# ADD_1_1.net
KiCad netlist of a schematic drawn in EAGLE
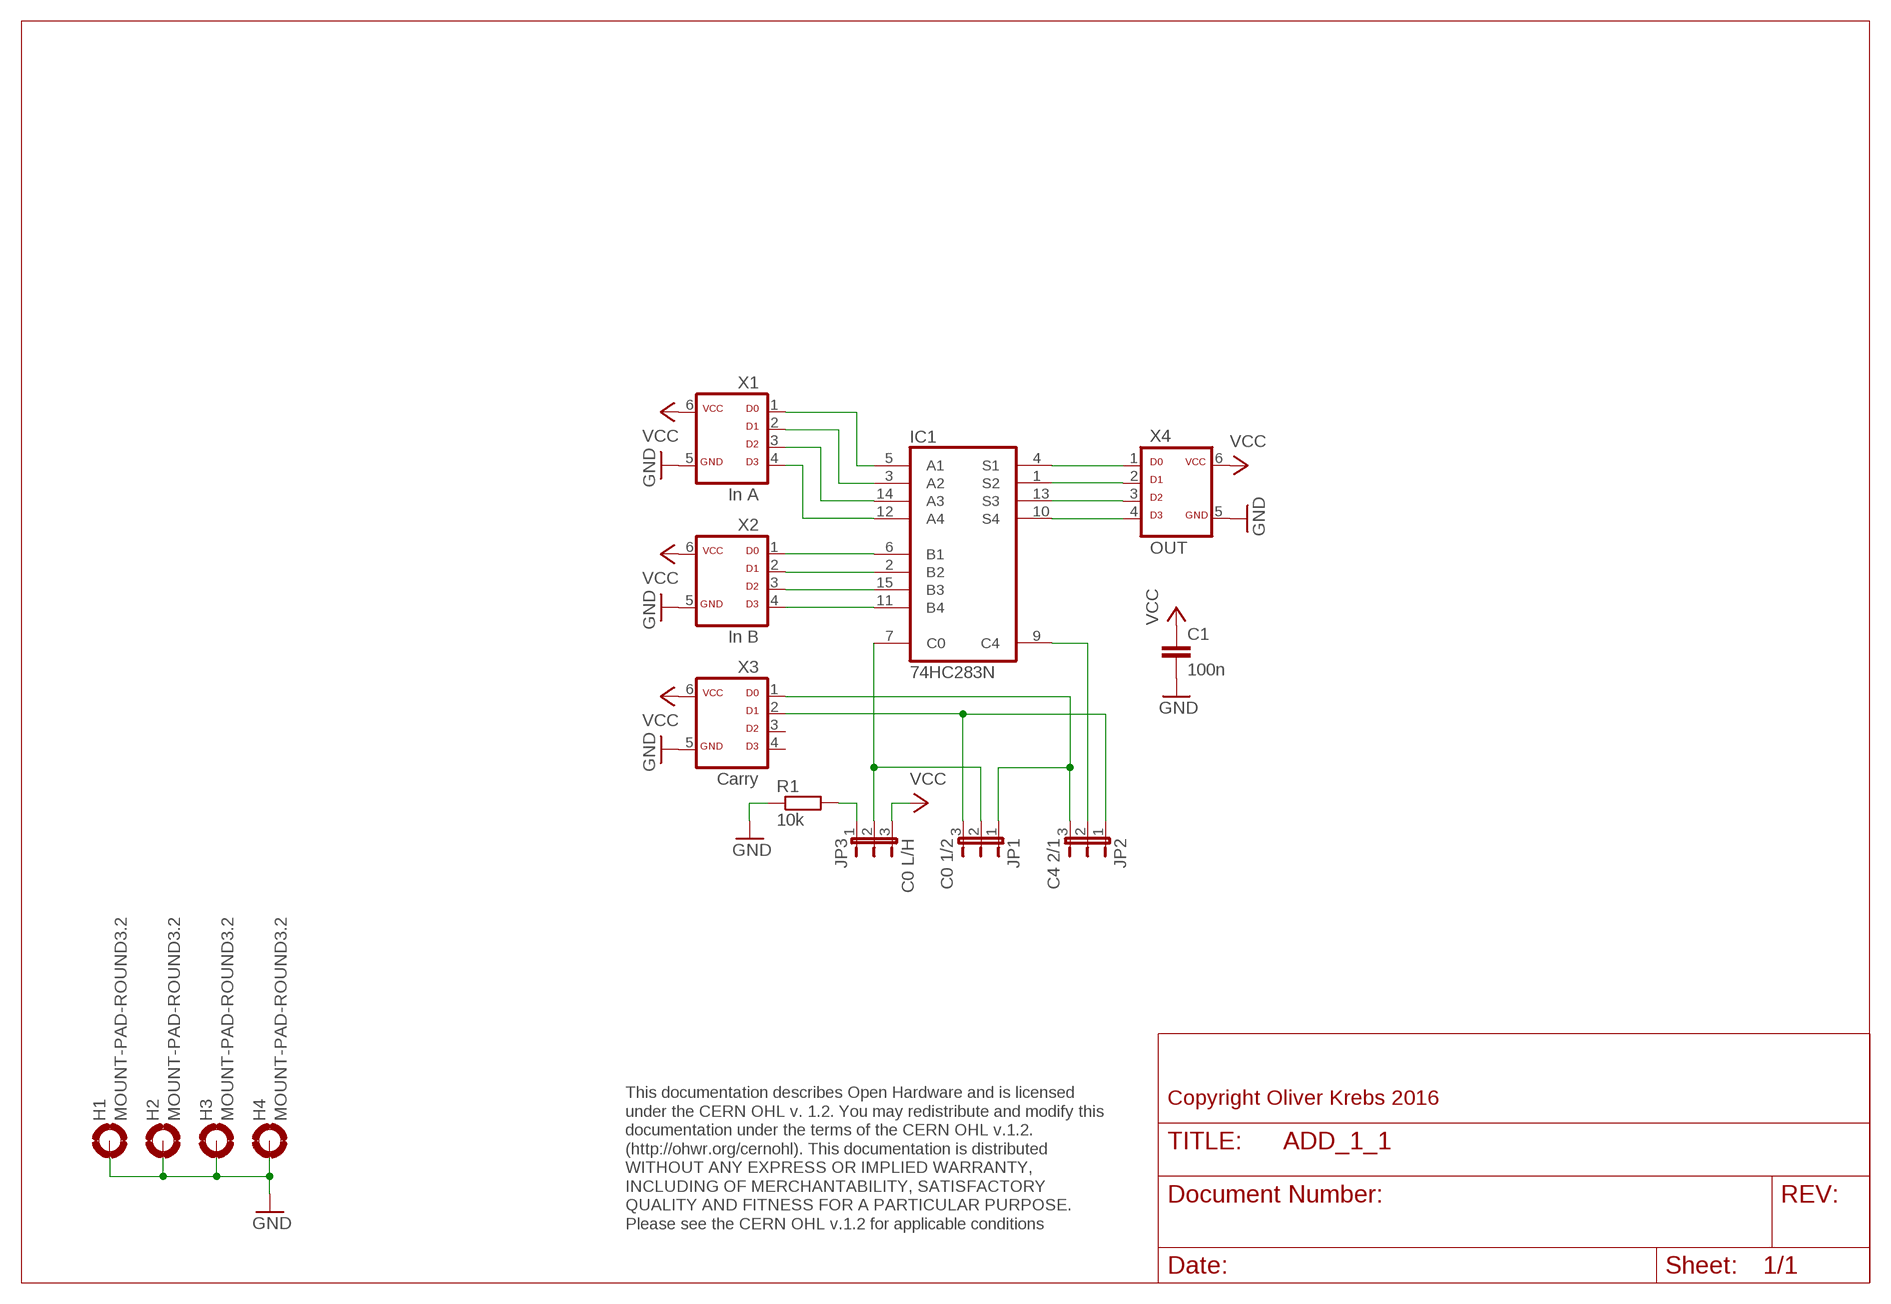
[diagram p0: schematic, sheet 1]

(export (version "E")
  (design (tool "Eeschema 10.0.6"))
  (components
    (comp (ref "C1")
      (value "100n")
      (footprint "eagle-import:C050-025X075")
      (libsource (lib "eagle-import") (part "C-EU050-025X075"))
    )
    (comp (ref "H1")
      (value "MOUNT-PAD-ROUND3.2")
      (footprint "eagle-import:3,2-PAD")
      (libsource (lib "eagle-import") (part "MOUNT-PAD-ROUND3.2"))
    )
    (comp (ref "H2")
      (value "MOUNT-PAD-ROUND3.2")
      (footprint "eagle-import:3,2-PAD")
      (libsource (lib "eagle-import") (part "MOUNT-PAD-ROUND3.2"))
    )
    (comp (ref "H3")
      (value "MOUNT-PAD-ROUND3.2")
      (footprint "eagle-import:3,2-PAD")
      (libsource (lib "eagle-import") (part "MOUNT-PAD-ROUND3.2"))
    )
    (comp (ref "H4")
      (value "MOUNT-PAD-ROUND3.2")
      (footprint "eagle-import:3,2-PAD")
      (libsource (lib "eagle-import") (part "MOUNT-PAD-ROUND3.2"))
    )
    (comp (ref "IC1")
      (value "74HC283N")
      (footprint "eagle-import:DIL16")
      (libsource (lib "eagle-import") (part "74283NHC"))
    )
    (comp (ref "JP1")
      (value "C0 1/2")
      (footprint "eagle-import:JP2")
      (libsource (lib "eagle-import") (part "JP2E"))
    )
    (comp (ref "JP2")
      (value "C4 2/1")
      (footprint "eagle-import:JP2")
      (libsource (lib "eagle-import") (part "JP2E"))
    )
    (comp (ref "JP3")
      (value "C0 L/H")
      (footprint "eagle-import:JP2")
      (libsource (lib "eagle-import") (part "JP2E"))
    )
    (comp (ref "R1")
      (value "10k")
      (footprint "eagle-import:0207_10")
      (libsource (lib "eagle-import") (part "R-EU_0207/10"))
    )
    (comp (ref "X1")
      (value "In A")
      (footprint "eagle-import:ML-6")
      (libsource (lib "eagle-import") (part "ML6D"))
    )
    (comp (ref "X2")
      (value "In B")
      (footprint "eagle-import:ML-6")
      (libsource (lib "eagle-import") (part "ML6D"))
    )
    (comp (ref "X3")
      (value "Carry")
      (footprint "eagle-import:ML-6")
      (libsource (lib "eagle-import") (part "ML6D"))
    )
    (comp (ref "X4")
      (value "OUT")
      (footprint "eagle-import:ML-6")
      (libsource (lib "eagle-import") (part "ML6D"))
    )
  )
  (nets
    (net (code "1") (name "GND") (class "Default")
      (node (ref "C1") (pin "2") (pinfunction "2_2") (pintype "passive"))
      (node (ref "H1") (pin "B3,2") (pinfunction "MOUNT_B3,2") (pintype "passive"))
      (node (ref "H2") (pin "B3,2") (pinfunction "MOUNT_B3,2") (pintype "passive"))
      (node (ref "H3") (pin "B3,2") (pinfunction "MOUNT_B3,2") (pintype "passive"))
      (node (ref "H4") (pin "B3,2") (pinfunction "MOUNT_B3,2") (pintype "passive"))
      (node (ref "R1") (pin "1") (pinfunction "1_1") (pintype "passive"))
      (node (ref "X1") (pin "5") (pinfunction "5_5") (pintype "passive"))
      (node (ref "X2") (pin "5") (pinfunction "5_5") (pintype "passive"))
      (node (ref "X3") (pin "5") (pinfunction "5_5") (pintype "passive"))
      (node (ref "X4") (pin "5") (pinfunction "5_5") (pintype "passive"))
    )
    (net (code "2") (name "Net-(IC1A-A1)") (class "Default")
      (node (ref "IC1") (pin "5") (pinfunction "A1_5") (pintype "input"))
      (node (ref "X1") (pin "1") (pinfunction "1_1") (pintype "passive"))
    )
    (net (code "3") (name "Net-(IC1A-A2)") (class "Default")
      (node (ref "IC1") (pin "3") (pinfunction "A2_3") (pintype "input"))
      (node (ref "X1") (pin "2") (pinfunction "2_2") (pintype "passive"))
    )
    (net (code "4") (name "Net-(IC1A-A3)") (class "Default")
      (node (ref "IC1") (pin "14") (pinfunction "A3_14") (pintype "input"))
      (node (ref "X1") (pin "3") (pinfunction "3_3") (pintype "passive"))
    )
    (net (code "5") (name "Net-(IC1A-A4)") (class "Default")
      (node (ref "IC1") (pin "12") (pinfunction "A4_12") (pintype "input"))
      (node (ref "X1") (pin "4") (pinfunction "4_4") (pintype "passive"))
    )
    (net (code "6") (name "Net-(IC1A-B1)") (class "Default")
      (node (ref "IC1") (pin "6") (pinfunction "B1_6") (pintype "input"))
      (node (ref "X2") (pin "1") (pinfunction "1_1") (pintype "passive"))
    )
    (net (code "7") (name "Net-(IC1A-B2)") (class "Default")
      (node (ref "IC1") (pin "2") (pinfunction "B2_2") (pintype "input"))
      (node (ref "X2") (pin "2") (pinfunction "2_2") (pintype "passive"))
    )
    (net (code "8") (name "Net-(IC1A-B3)") (class "Default")
      (node (ref "IC1") (pin "15") (pinfunction "B3_15") (pintype "input"))
      (node (ref "X2") (pin "3") (pinfunction "3_3") (pintype "passive"))
    )
    (net (code "9") (name "Net-(IC1A-B4)") (class "Default")
      (node (ref "IC1") (pin "11") (pinfunction "B4_11") (pintype "input"))
      (node (ref "X2") (pin "4") (pinfunction "4_4") (pintype "passive"))
    )
    (net (code "10") (name "Net-(IC1A-C0)") (class "Default")
      (node (ref "IC1") (pin "7") (pinfunction "C0_7") (pintype "input"))
      (node (ref "JP1") (pin "2") (pinfunction "2_2") (pintype "passive"))
      (node (ref "JP3") (pin "2") (pinfunction "2_2") (pintype "passive"))
    )
    (net (code "11") (name "Net-(IC1A-C4)") (class "Default")
      (node (ref "IC1") (pin "9") (pinfunction "C4_9") (pintype "output"))
      (node (ref "JP2") (pin "2") (pinfunction "2_2") (pintype "passive"))
    )
    (net (code "12") (name "Net-(IC1A-S1)") (class "Default")
      (node (ref "IC1") (pin "4") (pinfunction "S1_4") (pintype "output"))
      (node (ref "X4") (pin "1") (pinfunction "1_1") (pintype "passive"))
    )
    (net (code "13") (name "Net-(IC1A-S2)") (class "Default")
      (node (ref "IC1") (pin "1") (pinfunction "S2_1") (pintype "output"))
      (node (ref "X4") (pin "2") (pinfunction "2_2") (pintype "passive"))
    )
    (net (code "14") (name "Net-(IC1A-S3)") (class "Default")
      (node (ref "IC1") (pin "13") (pinfunction "S3_13") (pintype "output"))
      (node (ref "X4") (pin "3") (pinfunction "3_3") (pintype "passive"))
    )
    (net (code "15") (name "Net-(IC1A-S4)") (class "Default")
      (node (ref "IC1") (pin "10") (pinfunction "S4_10") (pintype "output"))
      (node (ref "X4") (pin "4") (pinfunction "4_4") (pintype "passive"))
    )
    (net (code "16") (name "Net-(JP1-Pad1)") (class "Default")
      (node (ref "JP1") (pin "1") (pinfunction "1_1") (pintype "passive"))
      (node (ref "JP2") (pin "3") (pinfunction "3_3") (pintype "passive"))
      (node (ref "X3") (pin "1") (pinfunction "1_1") (pintype "passive"))
    )
    (net (code "17") (name "Net-(JP1-Pad3)") (class "Default")
      (node (ref "JP1") (pin "3") (pinfunction "3_3") (pintype "passive"))
      (node (ref "JP2") (pin "1") (pinfunction "1_1") (pintype "passive"))
      (node (ref "X3") (pin "2") (pinfunction "2_2") (pintype "passive"))
    )
    (net (code "18") (name "Net-(JP3-Pad1)") (class "Default")
      (node (ref "JP3") (pin "1") (pinfunction "1_1") (pintype "passive"))
      (node (ref "R1") (pin "2") (pinfunction "2_2") (pintype "passive"))
    )
    (net (code "19") (name "VCC") (class "Default")
      (node (ref "C1") (pin "1") (pinfunction "1_1") (pintype "passive"))
      (node (ref "JP3") (pin "3") (pinfunction "3_3") (pintype "passive"))
      (node (ref "X1") (pin "6") (pinfunction "6_6") (pintype "passive"))
      (node (ref "X2") (pin "6") (pinfunction "6_6") (pintype "passive"))
      (node (ref "X3") (pin "6") (pinfunction "6_6") (pintype "passive"))
      (node (ref "X4") (pin "6") (pinfunction "6_6") (pintype "passive"))
    )
    (net (code "20") (name "unconnected-(X3-Pad3)") (class "Default")
      (node (ref "X3") (pin "3") (pinfunction "3_3") (pintype "passive"))
    )
    (net (code "21") (name "unconnected-(X3-Pad4)") (class "Default")
      (node (ref "X3") (pin "4") (pinfunction "4_4") (pintype "passive"))
    )
  )
)
